# Connectors.net
KiCad netlist of a schematic drawn in Altium Designer
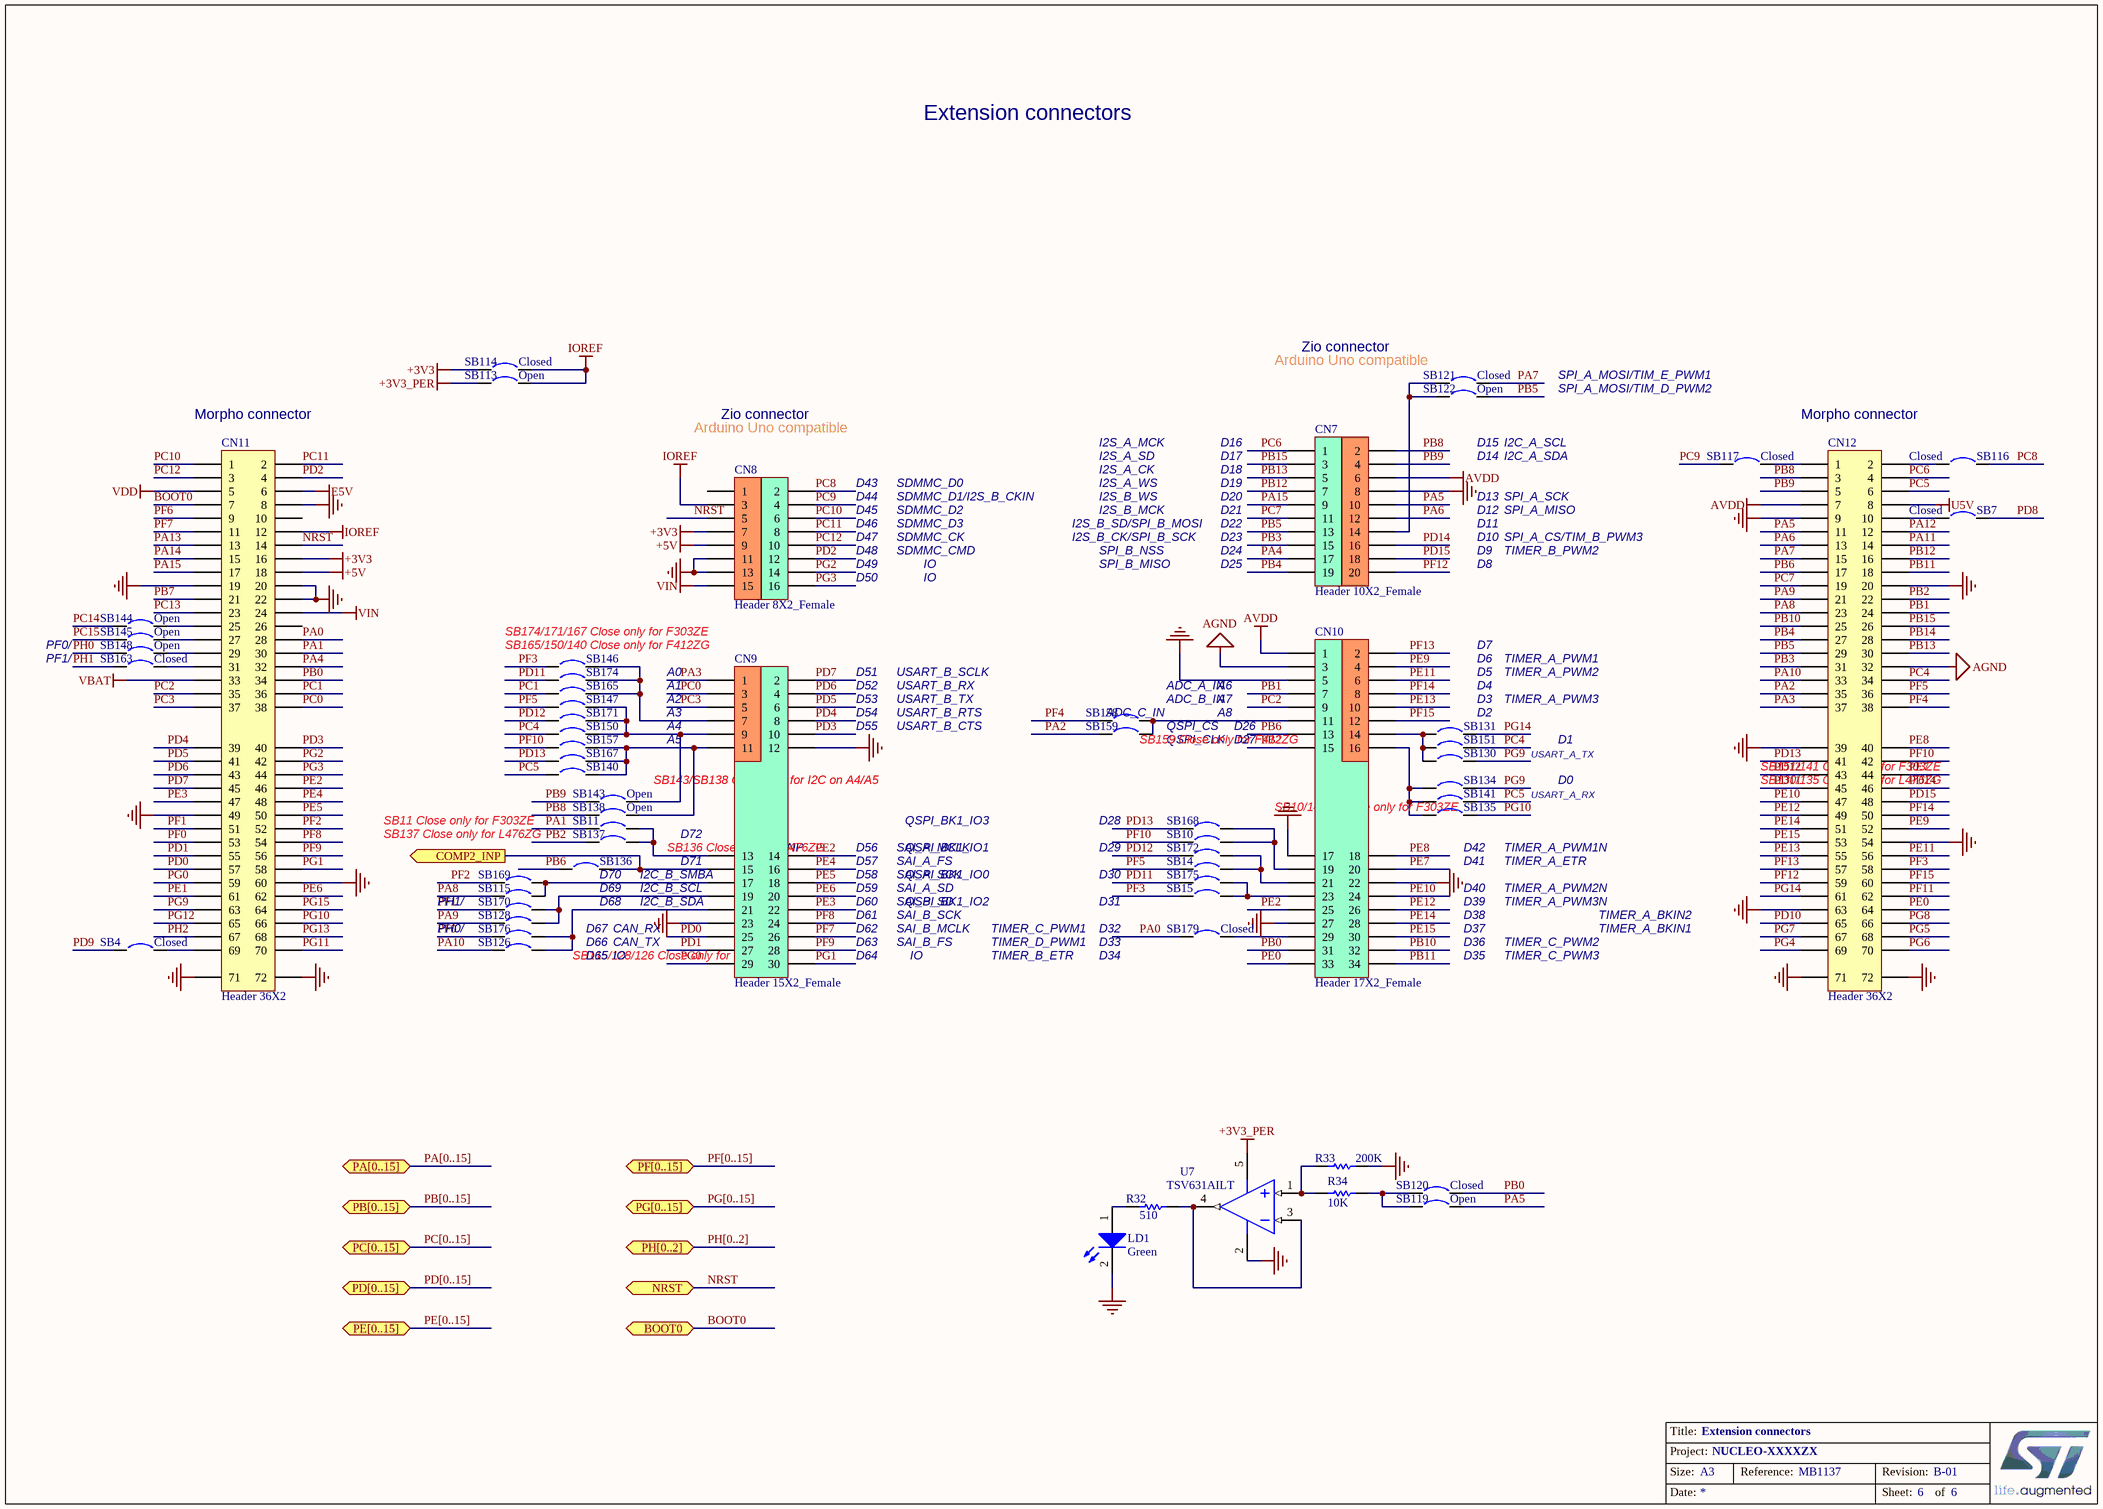
[diagram p0: Connectors.SchDoc]

(export (version "E")
  (design (tool "Eeschema 10.0.6"))
  (components
    (comp (ref "CN7")
      (value "Header 10X2_Female")
      (footprint "HDR_10x2_2R54_V_F")
      (description "Header, 10-Pin, Dual row,female")
      (fields (field (name "PUBLISHER") "Altium Limited"))
      (libsource (lib "MB1137") (part "Header 10X2_Female"))
    )
    (comp (ref "CN8")
      (value "Header 8X2_Female")
      (footprint "HDR_8x2_2R54_V_F")
      (description "Header, 8-Pin, Dual row,female")
      (fields (field (name "PUBLISHER") "Altium Limited"))
      (libsource (lib "MB1137") (part "Header 8X2_Female"))
    )
    (comp (ref "CN9")
      (value "Header 15X2_Female")
      (footprint "HDR_15x2_2R54_V_F")
      (description "Header, 15-Pin, Dual row,female")
      (fields (field (name "PUBLISHER") "Altium Limited"))
      (libsource (lib "MB1137") (part "Header 15X2_Female"))
    )
    (comp (ref "CN10")
      (value "Header 17X2_Female")
      (footprint "HDR_17x2_2R54_V_F")
      (description "Header, 17-Pin, Dual row,female")
      (fields (field (name "PUBLISHER") "Altium Limited"))
      (libsource (lib "MB1137") (part "Header 17X2_Female"))
    )
    (comp (ref "CN11")
      (value "Header 36X2")
      (footprint "HDR_2x36_2R54_V_M")
      (description "Header, 36-Pin, Dual row")
      (fields (field (name "PUBLISHER") "Altium Limited"))
      (libsource (lib "MB1137") (part "Header 36X2"))
    )
    (comp (ref "CN12")
      (value "Header 36X2")
      (footprint "HDR_2x36_2R54_V_M")
      (description "Header, 36-Pin, Dual row")
      (fields (field (name "PUBLISHER") "Altium Limited"))
      (libsource (lib "MB1137") (part "Header 36X2"))
    )
    (comp (ref "LD1")
      (value "Green")
      (footprint "0603D-G")
      (description "Typical RED, GREEN, YELLOW, AMBER GaAs LED")
      (fields (field (name "PUBLISHER") "Altium Limited"))
      (libsource (lib "Miscellaneous Devices") (part "LED2"))
    )
    (comp (ref "R32")
      (value "510")
      (footprint "0603R")
      (description "Resistor")
      (fields (field (name "PUBLISHER") "Altium Limited"))
      (libsource (lib "Miscellaneous Devices") (part "Res1"))
    )
    (comp (ref "R33")
      (value "200K")
      (footprint "0603R")
      (description "Resistor")
      (fields (field (name "PUBLISHER") "Altium Limited"))
      (libsource (lib "Miscellaneous Devices") (part "res1"))
    )
    (comp (ref "R34")
      (value "10K")
      (footprint "0603R")
      (description "Resistor")
      (fields (field (name "PUBLISHER") "Altium Limited"))
      (libsource (lib "Miscellaneous Devices") (part "res1"))
    )
    (comp (ref "SB4")
      (value "Closed")
      (footprint "SB_0603")
      (description "Circuit Breaker")
      (fields (field (name "PUBLISHER") "Altium Limited"))
      (libsource (lib "MB1167") (part "Circuit Breaker_close"))
    )
    (comp (ref "SB7")
      (value "Closed")
      (footprint "SB_0603")
      (description "Circuit Breaker")
      (fields (field (name "PUBLISHER") "Altium Limited"))
      (libsource (lib "MB1167") (part "Circuit Breaker_close"))
    )
    (comp (ref "SB10")
      (value "Circuit Breaker")
      (footprint "SB_0603")
      (fields (field (name "PUBLISHER") "Altium Limited"))
      (libsource (lib "") (part "Circuit Breaker_1"))
    )
    (comp (ref "SB11")
      (value "Circuit Breaker")
      (footprint "SB_0603")
      (fields (field (name "PUBLISHER") "Altium Limited"))
      (libsource (lib "MCD_TOOLS") (part "Circuit Breaker"))
    )
    (comp (ref "SB14")
      (value "Circuit Breaker")
      (footprint "SB_0603")
      (fields (field (name "PUBLISHER") "Altium Limited"))
      (libsource (lib "") (part "Circuit Breaker_1"))
    )
    (comp (ref "SB15")
      (value "Circuit Breaker")
      (footprint "SB_0603")
      (fields (field (name "PUBLISHER") "Altium Limited"))
      (libsource (lib "") (part "Circuit Breaker_1"))
    )
    (comp (ref "SB113")
      (value "Open")
      (footprint "SB_0603")
      (description "Circuit Breaker")
      (fields (field (name "PUBLISHER") "Altium Limited"))
      (libsource (lib "MB1167") (part "Circuit Breaker"))
    )
    (comp (ref "SB114")
      (value "Closed")
      (footprint "SB_0603")
      (description "Circuit Breaker")
      (fields (field (name "PUBLISHER") "Altium Limited"))
      (libsource (lib "MB1167") (part "Circuit Breaker_close"))
    )
    (comp (ref "SB115")
      (value "Circuit Breaker")
      (footprint "SB_0603")
      (fields (field (name "PUBLISHER") "Altium Limited"))
      (libsource (lib "MCD_TOOLS") (part "Circuit Breaker"))
    )
    (comp (ref "SB116")
      (value "Closed")
      (footprint "SB_0603")
      (description "Circuit Breaker")
      (fields (field (name "PUBLISHER") "Altium Limited"))
      (libsource (lib "") (part "Circuit Breaker_close_1"))
    )
    (comp (ref "SB117")
      (value "Closed")
      (footprint "SB_0603")
      (description "Circuit Breaker")
      (fields (field (name "PUBLISHER") "Altium Limited"))
      (libsource (lib "MB1167") (part "Circuit Breaker_close"))
    )
    (comp (ref "SB119")
      (value "Open")
      (footprint "SB_0603")
      (description "Circuit Breaker")
      (fields (field (name "PUBLISHER") "Altium Limited"))
      (libsource (lib "MB1167") (part "Circuit Breaker"))
    )
    (comp (ref "SB120")
      (value "Closed")
      (footprint "SB_0603")
      (description "Circuit Breaker")
      (fields (field (name "PUBLISHER") "Altium Limited"))
      (libsource (lib "") (part "Circuit Breaker_close_1"))
    )
    (comp (ref "SB121")
      (value "Closed")
      (footprint "SB_0603")
      (description "Circuit Breaker")
      (fields (field (name "PUBLISHER") "Altium Limited"))
      (libsource (lib "MB1167") (part "Circuit Breaker_close"))
    )
    (comp (ref "SB122")
      (value "Open")
      (footprint "SB_0603")
      (description "Circuit Breaker")
      (fields (field (name "PUBLISHER") "Altium Limited"))
      (libsource (lib "MB1167") (part "Circuit Breaker"))
    )
    (comp (ref "SB126")
      (value "Circuit Breaker")
      (footprint "SB_0603")
      (fields (field (name "PUBLISHER") "Altium Limited"))
      (libsource (lib "MCD_TOOLS") (part "Circuit Breaker"))
    )
    (comp (ref "SB128")
      (value "Circuit Breaker")
      (footprint "SB_0603")
      (fields (field (name "PUBLISHER") "Altium Limited"))
      (libsource (lib "MCD_TOOLS") (part "Circuit Breaker"))
    )
    (comp (ref "SB130")
      (value "Circuit Breaker")
      (footprint "SB_0603")
      (fields (field (name "PUBLISHER") "Altium Limited"))
      (libsource (lib "MCD_TOOLS") (part "Circuit Breaker"))
    )
    (comp (ref "SB131")
      (value "Circuit Breaker")
      (footprint "SB_0603")
      (fields (field (name "PUBLISHER") "Altium Limited"))
      (libsource (lib "MCD_TOOLS") (part "Circuit Breaker"))
    )
    (comp (ref "SB134")
      (value "Circuit Breaker")
      (footprint "SB_0603")
      (fields (field (name "PUBLISHER") "Altium Limited"))
      (libsource (lib "MCD_TOOLS") (part "Circuit Breaker"))
    )
    (comp (ref "SB135")
      (value "Circuit Breaker")
      (footprint "SB_0603")
      (fields (field (name "PUBLISHER") "Altium Limited"))
      (libsource (lib "MCD_TOOLS") (part "Circuit Breaker"))
    )
    (comp (ref "SB136")
      (value "Circuit Breaker")
      (footprint "SB_0603")
      (fields (field (name "PUBLISHER") "Altium Limited"))
      (libsource (lib "MCD_TOOLS") (part "Circuit Breaker"))
    )
    (comp (ref "SB137")
      (value "Circuit Breaker")
      (footprint "SB_0603")
      (fields (field (name "PUBLISHER") "Altium Limited"))
      (libsource (lib "MCD_TOOLS") (part "Circuit Breaker"))
    )
    (comp (ref "SB138")
      (value "Open")
      (footprint "SB_0603")
      (description "Circuit Breaker")
      (fields (field (name "PUBLISHER") "Altium Limited"))
      (libsource (lib "") (part "Circuit Breaker_1"))
    )
    (comp (ref "SB140")
      (value "Circuit Breaker")
      (footprint "SB_0603")
      (fields (field (name "PUBLISHER") "Altium Limited"))
      (libsource (lib "MCD_TOOLS") (part "Circuit Breaker"))
    )
    (comp (ref "SB141")
      (value "Circuit Breaker")
      (footprint "SB_0603")
      (fields (field (name "PUBLISHER") "Altium Limited"))
      (libsource (lib "MCD_TOOLS") (part "Circuit Breaker"))
    )
    (comp (ref "SB143")
      (value "Open")
      (footprint "SB_0603")
      (description "Circuit Breaker")
      (fields (field (name "PUBLISHER") "Altium Limited"))
      (libsource (lib "") (part "Circuit Breaker_1"))
    )
    (comp (ref "SB144")
      (value "Open")
      (footprint "SB_0603")
      (description "Circuit Breaker")
      (fields (field (name "PUBLISHER") "Altium Limited"))
      (libsource (lib "MB1167") (part "Circuit Breaker"))
    )
    (comp (ref "SB145")
      (value "Open")
      (footprint "SB_0603")
      (description "Circuit Breaker")
      (fields (field (name "PUBLISHER") "Altium Limited"))
      (libsource (lib "MB1167") (part "Circuit Breaker"))
    )
    (comp (ref "SB146")
      (value "Circuit Breaker")
      (footprint "SB_0603")
      (fields (field (name "PUBLISHER") "Altium Limited"))
      (libsource (lib "MCD_TOOLS") (part "Circuit Breaker"))
    )
    (comp (ref "SB147")
      (value "Circuit Breaker")
      (footprint "SB_0603")
      (fields (field (name "PUBLISHER") "Altium Limited"))
      (libsource (lib "MCD_TOOLS") (part "Circuit Breaker"))
    )
    (comp (ref "SB148")
      (value "Open")
      (footprint "SB_0603")
      (description "Circuit Breaker")
      (fields (field (name "PUBLISHER") "Altium Limited"))
      (libsource (lib "MB1167") (part "Circuit Breaker"))
    )
    (comp (ref "SB150")
      (value "Circuit Breaker")
      (footprint "SB_0603")
      (fields (field (name "PUBLISHER") "Altium Limited"))
      (libsource (lib "MCD_TOOLS") (part "Circuit Breaker"))
    )
    (comp (ref "SB151")
      (value "Circuit Breaker")
      (footprint "SB_0603")
      (fields (field (name "PUBLISHER") "Altium Limited"))
      (libsource (lib "MCD_TOOLS") (part "Circuit Breaker"))
    )
    (comp (ref "SB157")
      (value "Circuit Breaker")
      (footprint "SB_0603")
      (fields (field (name "PUBLISHER") "Altium Limited"))
      (libsource (lib "MCD_TOOLS") (part "Circuit Breaker"))
    )
    (comp (ref "SB158")
      (value "Circuit Breaker")
      (footprint "SB_0603")
      (fields (field (name "PUBLISHER") "Altium Limited"))
      (libsource (lib "") (part "Circuit Breaker_1"))
    )
    (comp (ref "SB159")
      (value "Circuit Breaker")
      (footprint "SB_0603")
      (fields (field (name "PUBLISHER") "Altium Limited"))
      (libsource (lib "") (part "Circuit Breaker_1"))
    )
    (comp (ref "SB163")
      (value "Closed")
      (footprint "SB_0603")
      (description "Circuit Breaker")
      (fields (field (name "PUBLISHER") "Altium Limited"))
      (libsource (lib "MB1167") (part "Circuit Breaker_close"))
    )
    (comp (ref "SB165")
      (value "Circuit Breaker")
      (footprint "SB_0603")
      (fields (field (name "PUBLISHER") "Altium Limited"))
      (libsource (lib "MCD_TOOLS") (part "Circuit Breaker"))
    )
    (comp (ref "SB167")
      (value "Circuit Breaker")
      (footprint "SB_0603")
      (fields (field (name "PUBLISHER") "Altium Limited"))
      (libsource (lib "MCD_TOOLS") (part "Circuit Breaker"))
    )
    (comp (ref "SB168")
      (value "Circuit Breaker")
      (footprint "SB_0603")
      (fields (field (name "PUBLISHER") "Altium Limited"))
      (libsource (lib "") (part "Circuit Breaker_1"))
    )
    (comp (ref "SB169")
      (value "Circuit Breaker")
      (footprint "SB_0603")
      (fields (field (name "PUBLISHER") "Altium Limited"))
      (libsource (lib "MCD_TOOLS") (part "Circuit Breaker"))
    )
    (comp (ref "SB170")
      (value "Circuit Breaker")
      (footprint "SB_0603")
      (fields (field (name "PUBLISHER") "Altium Limited"))
      (libsource (lib "MCD_TOOLS") (part "Circuit Breaker"))
    )
    (comp (ref "SB171")
      (value "Circuit Breaker")
      (footprint "SB_0603")
      (fields (field (name "PUBLISHER") "Altium Limited"))
      (libsource (lib "MCD_TOOLS") (part "Circuit Breaker"))
    )
    (comp (ref "SB172")
      (value "Circuit Breaker")
      (footprint "SB_0603")
      (fields (field (name "PUBLISHER") "Altium Limited"))
      (libsource (lib "") (part "Circuit Breaker_1"))
    )
    (comp (ref "SB174")
      (value "Circuit Breaker")
      (footprint "SB_0603")
      (fields (field (name "PUBLISHER") "Altium Limited"))
      (libsource (lib "MCD_TOOLS") (part "Circuit Breaker"))
    )
    (comp (ref "SB175")
      (value "Circuit Breaker")
      (footprint "SB_0603")
      (fields (field (name "PUBLISHER") "Altium Limited"))
      (libsource (lib "") (part "Circuit Breaker_1"))
    )
    (comp (ref "SB176")
      (value "Circuit Breaker")
      (footprint "SB_0603")
      (fields (field (name "PUBLISHER") "Altium Limited"))
      (libsource (lib "MCD_TOOLS") (part "Circuit Breaker"))
    )
    (comp (ref "SB179")
      (value "Closed")
      (footprint "SB_0603")
      (description "Circuit Breaker")
      (fields (field (name "PUBLISHER") "Altium Limited"))
      (libsource (lib "MB1167") (part "Circuit Breaker_close"))
    )
    (comp (ref "U7")
      (value "TSV631AILT")
      (footprint "SOT-23-5L")
      (libsource (lib "MB988") (part "TSV631AILT"))
    )
  )
  (nets
    (net (code "1") (name "+3V3") (class "Default")
      (node (ref "CN11") (pin "16") (pinfunction "16_16") (pintype "passive"))
      (node (ref "CN8") (pin "7") (pinfunction "7_7") (pintype "passive"))
      (node (ref "SB114") (pin "1") (pinfunction "1_1") (pintype "passive"))
    )
    (net (code "2") (name "+3V3_PER") (class "Default")
      (node (ref "SB113") (pin "1") (pinfunction "1_1") (pintype "passive"))
      (node (ref "U7") (pin "5") (pinfunction "VCC_5") (pintype "power_in"))
    )
    (net (code "3") (name "+5V") (class "Default")
      (node (ref "CN11") (pin "18") (pinfunction "18_18") (pintype "passive"))
      (node (ref "CN8") (pin "9") (pinfunction "9_9") (pintype "passive"))
    )
    (net (code "4") (name "/BOOT0") (class "Default")
      (node (ref "CN11") (pin "7") (pinfunction "7_7") (pintype "passive"))
    )
    (net (code "5") (name "/COMP2_INP") (class "Default")
      (node (ref "CN9") (pin "15") (pinfunction "15_15") (pintype "passive"))
      (node (ref "SB136") (pin "1") (pinfunction "1_1") (pintype "passive"))
    )
    (net (code "6") (name "/NRST") (class "Default")
      (node (ref "CN11") (pin "14") (pinfunction "14_14") (pintype "passive"))
      (node (ref "CN8") (pin "5") (pinfunction "5_5") (pintype "passive"))
    )
    (net (code "7") (name "/PA0") (class "Default")
      (node (ref "CN11") (pin "28") (pinfunction "28_28") (pintype "passive"))
      (node (ref "SB179") (pin "1") (pinfunction "1_1") (pintype "passive"))
    )
    (net (code "8") (name "/PA1") (class "Default")
      (node (ref "CN11") (pin "30") (pinfunction "30_30") (pintype "passive"))
      (node (ref "SB11") (pin "2") (pinfunction "2_2") (pintype "passive"))
    )
    (net (code "9") (name "/PA2") (class "Default")
      (node (ref "CN12") (pin "35") (pinfunction "35_35") (pintype "passive"))
      (node (ref "SB159") (pin "1") (pinfunction "1_1") (pintype "passive"))
    )
    (net (code "10") (name "/PA3") (class "Default")
      (node (ref "CN12") (pin "37") (pinfunction "37_37") (pintype "passive"))
      (node (ref "CN9") (pin "1") (pinfunction "1_1") (pintype "passive"))
    )
    (net (code "11") (name "/PA4") (class "Default")
      (node (ref "CN11") (pin "32") (pinfunction "32_32") (pintype "passive"))
      (node (ref "CN7") (pin "17") (pinfunction "17_17") (pintype "passive"))
    )
    (net (code "12") (name "/PA5") (class "Default")
      (node (ref "CN12") (pin "11") (pinfunction "11_11") (pintype "passive"))
      (node (ref "CN7") (pin "10") (pinfunction "10_10") (pintype "passive"))
      (node (ref "SB119") (pin "2") (pinfunction "2_2") (pintype "passive"))
    )
    (net (code "13") (name "/PA6") (class "Default")
      (node (ref "CN12") (pin "13") (pinfunction "13_13") (pintype "passive"))
      (node (ref "CN7") (pin "12") (pinfunction "12_12") (pintype "passive"))
    )
    (net (code "14") (name "/PA7") (class "Default")
      (node (ref "CN12") (pin "15") (pinfunction "15_15") (pintype "passive"))
      (node (ref "SB121") (pin "2") (pinfunction "2_2") (pintype "passive"))
    )
    (net (code "15") (name "/PA8") (class "Default")
      (node (ref "CN12") (pin "23") (pinfunction "23_23") (pintype "passive"))
      (node (ref "SB115") (pin "2") (pinfunction "2_2") (pintype "passive"))
    )
    (net (code "16") (name "/PA9") (class "Default")
      (node (ref "CN12") (pin "21") (pinfunction "21_21") (pintype "passive"))
      (node (ref "SB128") (pin "2") (pinfunction "2_2") (pintype "passive"))
    )
    (net (code "17") (name "/PA10") (class "Default")
      (node (ref "CN12") (pin "33") (pinfunction "33_33") (pintype "passive"))
      (node (ref "SB126") (pin "2") (pinfunction "2_2") (pintype "passive"))
    )
    (net (code "18") (name "/PA11") (class "Default")
      (node (ref "CN12") (pin "14") (pinfunction "14_14") (pintype "passive"))
    )
    (net (code "19") (name "/PA12") (class "Default")
      (node (ref "CN12") (pin "12") (pinfunction "12_12") (pintype "passive"))
    )
    (net (code "20") (name "/PA13") (class "Default")
      (node (ref "CN11") (pin "13") (pinfunction "13_13") (pintype "passive"))
    )
    (net (code "21") (name "/PA14") (class "Default")
      (node (ref "CN11") (pin "15") (pinfunction "15_15") (pintype "passive"))
    )
    (net (code "22") (name "/PA15") (class "Default")
      (node (ref "CN11") (pin "17") (pinfunction "17_17") (pintype "passive"))
      (node (ref "CN7") (pin "9") (pinfunction "9_9") (pintype "passive"))
    )
    (net (code "24") (name "/PB0") (class "Default")
      (node (ref "CN10") (pin "31") (pinfunction "31_31") (pintype "passive"))
      (node (ref "CN11") (pin "34") (pinfunction "34_34") (pintype "passive"))
      (node (ref "SB120") (pin "1") (pinfunction "1_1") (pintype "passive"))
    )
    (net (code "25") (name "/PB1") (class "Default")
      (node (ref "CN10") (pin "7") (pinfunction "7_7") (pintype "passive"))
      (node (ref "CN12") (pin "24") (pinfunction "24_24") (pintype "passive"))
    )
    (net (code "26") (name "/PB2") (class "Default")
      (node (ref "CN10") (pin "15") (pinfunction "15_15") (pintype "passive"))
      (node (ref "CN12") (pin "22") (pinfunction "22_22") (pintype "passive"))
      (node (ref "SB137") (pin "2") (pinfunction "2_2") (pintype "passive"))
    )
    (net (code "27") (name "/PB3") (class "Default")
      (node (ref "CN12") (pin "31") (pinfunction "31_31") (pintype "passive"))
      (node (ref "CN7") (pin "15") (pinfunction "15_15") (pintype "passive"))
    )
    (net (code "28") (name "/PB4") (class "Default")
      (node (ref "CN12") (pin "27") (pinfunction "27_27") (pintype "passive"))
      (node (ref "CN7") (pin "19") (pinfunction "19_19") (pintype "passive"))
    )
    (net (code "29") (name "/PB5") (class "Default")
      (node (ref "CN12") (pin "29") (pinfunction "29_29") (pintype "passive"))
      (node (ref "CN7") (pin "13") (pinfunction "13_13") (pintype "passive"))
      (node (ref "SB122") (pin "2") (pinfunction "2_2") (pintype "passive"))
    )
    (net (code "30") (name "/PB6") (class "Default")
      (node (ref "CN10") (pin "13") (pinfunction "13_13") (pintype "passive"))
      (node (ref "CN12") (pin "17") (pinfunction "17_17") (pintype "passive"))
      (node (ref "SB136") (pin "2") (pinfunction "2_2") (pintype "passive"))
    )
    (net (code "31") (name "/PB7") (class "Default")
      (node (ref "CN11") (pin "21") (pinfunction "21_21") (pintype "passive"))
    )
    (net (code "32") (name "/PB8") (class "Default")
      (node (ref "CN12") (pin "3") (pinfunction "3_3") (pintype "passive"))
      (node (ref "CN7") (pin "2") (pinfunction "2_2") (pintype "passive"))
      (node (ref "SB138") (pin "2") (pinfunction "2_2") (pintype "passive"))
    )
    (net (code "33") (name "/PB9") (class "Default")
      (node (ref "CN12") (pin "5") (pinfunction "5_5") (pintype "passive"))
      (node (ref "CN7") (pin "4") (pinfunction "4_4") (pintype "passive"))
      (node (ref "SB143") (pin "2") (pinfunction "2_2") (pintype "passive"))
    )
    (net (code "34") (name "/PB10") (class "Default")
      (node (ref "CN10") (pin "32") (pinfunction "32_32") (pintype "passive"))
      (node (ref "CN12") (pin "25") (pinfunction "25_25") (pintype "passive"))
    )
    (net (code "35") (name "/PB11") (class "Default")
      (node (ref "CN10") (pin "34") (pinfunction "34_34") (pintype "passive"))
      (node (ref "CN12") (pin "18") (pinfunction "18_18") (pintype "passive"))
    )
    (net (code "36") (name "/PB12") (class "Default")
      (node (ref "CN12") (pin "16") (pinfunction "16_16") (pintype "passive"))
      (node (ref "CN7") (pin "7") (pinfunction "7_7") (pintype "passive"))
    )
    (net (code "37") (name "/PB13") (class "Default")
      (node (ref "CN12") (pin "30") (pinfunction "30_30") (pintype "passive"))
      (node (ref "CN7") (pin "5") (pinfunction "5_5") (pintype "passive"))
    )
    (net (code "38") (name "/PB14") (class "Default")
      (node (ref "CN12") (pin "28") (pinfunction "28_28") (pintype "passive"))
    )
    (net (code "39") (name "/PB15") (class "Default")
      (node (ref "CN12") (pin "26") (pinfunction "26_26") (pintype "passive"))
      (node (ref "CN7") (pin "3") (pinfunction "3_3") (pintype "passive"))
    )
    (net (code "41") (name "/PC0") (class "Default")
      (node (ref "CN11") (pin "38") (pinfunction "38_38") (pintype "passive"))
      (node (ref "CN9") (pin "3") (pinfunction "3_3") (pintype "passive"))
    )
    (net (code "42") (name "/PC1") (class "Default")
      (node (ref "CN11") (pin "36") (pinfunction "36_36") (pintype "passive"))
      (node (ref "SB165") (pin "2") (pinfunction "2_2") (pintype "passive"))
    )
    (net (code "43") (name "/PC2") (class "Default")
      (node (ref "CN10") (pin "9") (pinfunction "9_9") (pintype "passive"))
      (node (ref "CN11") (pin "35") (pinfunction "35_35") (pintype "passive"))
    )
    (net (code "44") (name "/PC3") (class "Default")
      (node (ref "CN11") (pin "37") (pinfunction "37_37") (pintype "passive"))
      (node (ref "CN9") (pin "5") (pinfunction "5_5") (pintype "passive"))
    )
    (net (code "45") (name "/PC4") (class "Default")
      (node (ref "CN12") (pin "34") (pinfunction "34_34") (pintype "passive"))
      (node (ref "SB150") (pin "2") (pinfunction "2_2") (pintype "passive"))
      (node (ref "SB151") (pin "1") (pinfunction "1_1") (pintype "passive"))
    )
    (net (code "46") (name "/PC5") (class "Default")
      (node (ref "CN12") (pin "6") (pinfunction "6_6") (pintype "passive"))
      (node (ref "SB140") (pin "2") (pinfunction "2_2") (pintype "passive"))
      (node (ref "SB141") (pin "1") (pinfunction "1_1") (pintype "passive"))
    )
    (net (code "47") (name "/PC6") (class "Default")
      (node (ref "CN12") (pin "4") (pinfunction "4_4") (pintype "passive"))
      (node (ref "CN7") (pin "1") (pinfunction "1_1") (pintype "passive"))
    )
    (net (code "48") (name "/PC7") (class "Default")
      (node (ref "CN12") (pin "19") (pinfunction "19_19") (pintype "passive"))
      (node (ref "CN7") (pin "11") (pinfunction "11_11") (pintype "passive"))
    )
    (net (code "49") (name "/PC8") (class "Default")
      (node (ref "CN8") (pin "2") (pinfunction "2_2") (pintype "passive"))
      (node (ref "SB116") (pin "1") (pinfunction "1_1") (pintype "passive"))
    )
    (net (code "50") (name "/PC9") (class "Default")
      (node (ref "CN8") (pin "4") (pinfunction "4_4") (pintype "passive"))
      (node (ref "SB117") (pin "1") (pinfunction "1_1") (pintype "passive"))
    )
    (net (code "51") (name "/PC10") (class "Default")
      (node (ref "CN11") (pin "1") (pinfunction "1_1") (pintype "passive"))
      (node (ref "CN8") (pin "6") (pinfunction "6_6") (pintype "passive"))
    )
    (net (code "52") (name "/PC11") (class "Default")
      (node (ref "CN11") (pin "2") (pinfunction "2_2") (pintype "passive"))
      (node (ref "CN8") (pin "8") (pinfunction "8_8") (pintype "passive"))
    )
    (net (code "53") (name "/PC12") (class "Default")
      (node (ref "CN11") (pin "3") (pinfunction "3_3") (pintype "passive"))
      (node (ref "CN8") (pin "10") (pinfunction "10_10") (pintype "passive"))
    )
    (net (code "54") (name "/PC13") (class "Default")
      (node (ref "CN11") (pin "23") (pinfunction "23_23") (pintype "passive"))
    )
    (net (code "55") (name "/PC14") (class "Default")
      (node (ref "SB144") (pin "1") (pinfunction "1_1") (pintype "passive"))
    )
    (net (code "56") (name "/PC15") (class "Default")
      (node (ref "SB145") (pin "1") (pinfunction "1_1") (pintype "passive"))
    )
    (net (code "58") (name "/PD0") (class "Default")
      (node (ref "CN11") (pin "57") (pinfunction "57_57") (pintype "passive"))
      (node (ref "CN9") (pin "25") (pinfunction "25_25") (pintype "passive"))
    )
    (net (code "59") (name "/PD1") (class "Default")
      (node (ref "CN11") (pin "55") (pinfunction "55_55") (pintype "passive"))
      (node (ref "CN9") (pin "27") (pinfunction "27_27") (pintype "passive"))
    )
    (net (code "60") (name "/PD2") (class "Default")
      (node (ref "CN11") (pin "4") (pinfunction "4_4") (pintype "passive"))
      (node (ref "CN8") (pin "12") (pinfunction "12_12") (pintype "passive"))
    )
    (net (code "61") (name "/PD3") (class "Default")
      (node (ref "CN11") (pin "40") (pinfunction "40_40") (pintype "passive"))
      (node (ref "CN9") (pin "10") (pinfunction "10_10") (pintype "passive"))
    )
    (net (code "62") (name "/PD4") (class "Default")
      (node (ref "CN11") (pin "39") (pinfunction "39_39") (pintype "passive"))
      (node (ref "CN9") (pin "8") (pinfunction "8_8") (pintype "passive"))
    )
    (net (code "63") (name "/PD5") (class "Default")
      (node (ref "CN11") (pin "41") (pinfunction "41_41") (pintype "passive"))
      (node (ref "CN9") (pin "6") (pinfunction "6_6") (pintype "passive"))
    )
    (net (code "64") (name "/PD6") (class "Default")
      (node (ref "CN11") (pin "43") (pinfunction "43_43") (pintype "passive"))
      (node (ref "CN9") (pin "4") (pinfunction "4_4") (pintype "passive"))
    )
    (net (code "65") (name "/PD7") (class "Default")
      (node (ref "CN11") (pin "45") (pinfunction "45_45") (pintype "passive"))
      (node (ref "CN9") (pin "2") (pinfunction "2_2") (pintype "passive"))
    )
    (net (code "66") (name "/PD8") (class "Default")
      (node (ref "SB7") (pin "2") (pinfunction "2_2") (pintype "passive"))
    )
    (net (code "67") (name "/PD9") (class "Default")
      (node (ref "SB4") (pin "1") (pinfunction "1_1") (pintype "passive"))
    )
    (net (code "68") (name "/PD10") (class "Default")
      (node (ref "CN12") (pin "65") (pinfunction "65_65") (pintype "passive"))
    )
    (net (code "69") (name "/PD11") (class "Default")
      (node (ref "CN12") (pin "45") (pinfunction "45_45") (pintype "passive"))
      (node (ref "SB174") (pin "2") (pinfunction "2_2") (pintype "passive"))
      (node (ref "SB175") (pin "1") (pinfunction "1_1") (pintype "passive"))
    )
    (net (code "70") (name "/PD12") (class "Default")
      (node (ref "CN12") (pin "43") (pinfunction "43_43") (pintype "passive"))
      (node (ref "SB171") (pin "2") (pinfunction "2_2") (pintype "passive"))
      (node (ref "SB172") (pin "1") (pinfunction "1_1") (pintype "passive"))
    )
    (net (code "71") (name "/PD13") (class "Default")
      (node (ref "CN12") (pin "41") (pinfunction "41_41") (pintype "passive"))
      (node (ref "SB167") (pin "2") (pinfunction "2_2") (pintype "passive"))
      (node (ref "SB168") (pin "1") (pinfunction "1_1") (pintype "passive"))
    )
    (net (code "72") (name "/PD14") (class "Default")
      (node (ref "CN12") (pin "46") (pinfunction "46_46") (pintype "passive"))
      (node (ref "CN7") (pin "16") (pinfunction "16_16") (pintype "passive"))
    )
    (net (code "73") (name "/PD15") (class "Default")
      (node (ref "CN12") (pin "48") (pinfunction "48_48") (pintype "passive"))
      (node (ref "CN7") (pin "18") (pinfunction "18_18") (pintype "passive"))
    )
    (net (code "75") (name "/PE0") (class "Default")
      (node (ref "CN10") (pin "33") (pinfunction "33_33") (pintype "passive"))
      (node (ref "CN12") (pin "64") (pinfunction "64_64") (pintype "passive"))
    )
    (net (code "76") (name "/PE1") (class "Default")
      (node (ref "CN11") (pin "61") (pinfunction "61_61") (pintype "passive"))
    )
    (net (code "77") (name "/PE2") (class "Default")
      (node (ref "CN10") (pin "25") (pinfunction "25_25") (pintype "passive"))
      (node (ref "CN11") (pin "46") (pinfunction "46_46") (pintype "passive"))
      (node (ref "CN9") (pin "14") (pinfunction "14_14") (pintype "passive"))
    )
    (net (code "78") (name "/PE3") (class "Default")
      (node (ref "CN11") (pin "47") (pinfunction "47_47") (pintype "passive"))
      (node (ref "CN9") (pin "22") (pinfunction "22_22") (pintype "passive"))
    )
    (net (code "79") (name "/PE4") (class "Default")
      (node (ref "CN11") (pin "48") (pinfunction "48_48") (pintype "passive"))
      (node (ref "CN9") (pin "16") (pinfunction "16_16") (pintype "passive"))
    )
    (net (code "80") (name "/PE5") (class "Default")
      (node (ref "CN11") (pin "50") (pinfunction "50_50") (pintype "passive"))
      (node (ref "CN9") (pin "18") (pinfunction "18_18") (pintype "passive"))
    )
    (net (code "81") (name "/PE6") (class "Default")
      (node (ref "CN11") (pin "62") (pinfunction "62_62") (pintype "passive"))
      (node (ref "CN9") (pin "20") (pinfunction "20_20") (pintype "passive"))
    )
    (net (code "82") (name "/PE7") (class "Default")
      (node (ref "CN10") (pin "20") (pinfunction "20_20") (pintype "passive"))
      (node (ref "CN12") (pin "44") (pinfunction "44_44") (pintype "passive"))
    )
    (net (code "83") (name "/PE8") (class "Default")
      (node (ref "CN10") (pin "18") (pinfunction "18_18") (pintype "passive"))
      (node (ref "CN12") (pin "40") (pinfunction "40_40") (pintype "passive"))
    )
    (net (code "84") (name "/PE9") (class "Default")
      (node (ref "CN10") (pin "4") (pinfunction "4_4") (pintype "passive"))
      (node (ref "CN12") (pin "52") (pinfunction "52_52") (pintype "passive"))
    )
    (net (code "85") (name "/PE10") (class "Default")
      (node (ref "CN10") (pin "24") (pinfunction "24_24") (pintype "passive"))
      (node (ref "CN12") (pin "47") (pinfunction "47_47") (pintype "passive"))
    )
    (net (code "86") (name "/PE11") (class "Default")
      (node (ref "CN10") (pin "6") (pinfunction "6_6") (pintype "passive"))
      (node (ref "CN12") (pin "56") (pinfunction "56_56") (pintype "passive"))
    )
    (net (code "87") (name "/PE12") (class "Default")
      (node (ref "CN10") (pin "26") (pinfunction "26_26") (pintype "passive"))
      (node (ref "CN12") (pin "49") (pinfunction "49_49") (pintype "passive"))
    )
    (net (code "88") (name "/PE13") (class "Default")
      (node (ref "CN10") (pin "10") (pinfunction "10_10") (pintype "passive"))
      (node (ref "CN12") (pin "55") (pinfunction "55_55") (pintype "passive"))
    )
    (net (code "89") (name "/PE14") (class "Default")
      (node (ref "CN10") (pin "28") (pinfunction "28_28") (pintype "passive"))
      (node (ref "CN12") (pin "51") (pinfunction "51_51") (pintype "passive"))
    )
    (net (code "90") (name "/PE15") (class "Default")
      (node (ref "CN10") (pin "30") (pinfunction "30_30") (pintype "passive"))
      (node (ref "CN12") (pin "53") (pinfunction "53_53") (pintype "passive"))
    )
    (net (code "92") (name "/PF0") (class "Default")
      (node (ref "CN11") (pin "53") (pinfunction "53_53") (pintype "passive"))
      (node (ref "SB176") (pin "2") (pinfunction "2_2") (pintype "passive"))
    )
    (net (code "93") (name "/PF1") (class "Default")
      (node (ref "CN11") (pin "51") (pinfunction "51_51") (pintype "passive"))
      (node (ref "SB170") (pin "2") (pinfunction "2_2") (pintype "passive"))
    )
    (net (code "94") (name "/PF2") (class "Default")
      (node (ref "CN11") (pin "52") (pinfunction "52_52") (pintype "passive"))
      (node (ref "SB169") (pin "2") (pinfunction "2_2") (pintype "passive"))
    )
    (net (code "95") (name "/PF3") (class "Default")
      (node (ref "CN12") (pin "58") (pinfunction "58_58") (pintype "passive"))
      (node (ref "SB146") (pin "2") (pinfunction "2_2") (pintype "passive"))
      (node (ref "SB15") (pin "1") (pinfunction "1_1") (pintype "passive"))
    )
    (net (code "96") (name "/PF4") (class "Default")
      (node (ref "CN12") (pin "38") (pinfunction "38_38") (pintype "passive"))
      (node (ref "SB158") (pin "1") (pinfunction "1_1") (pintype "passive"))
    )
    (net (code "97") (name "/PF5") (class "Default")
      (node (ref "CN12") (pin "36") (pinfunction "36_36") (pintype "passive"))
      (node (ref "SB14") (pin "1") (pinfunction "1_1") (pintype "passive"))
      (node (ref "SB147") (pin "2") (pinfunction "2_2") (pintype "passive"))
    )
    (net (code "98") (name "/PF6") (class "Default")
      (node (ref "CN11") (pin "9") (pinfunction "9_9") (pintype "passive"))
    )
    (net (code "99") (name "/PF7") (class "Default")
      (node (ref "CN11") (pin "11") (pinfunction "11_11") (pintype "passive"))
      (node (ref "CN9") (pin "26") (pinfunction "26_26") (pintype "passive"))
    )
    (net (code "100") (name "/PF8") (class "Default")
      (node (ref "CN11") (pin "54") (pinfunction "54_54") (pintype "passive"))
      (node (ref "CN9") (pin "24") (pinfunction "24_24") (pintype "passive"))
    )
    (net (code "101") (name "/PF9") (class "Default")
      (node (ref "CN11") (pin "56") (pinfunction "56_56") (pintype "passive"))
      (node (ref "CN9") (pin "28") (pinfunction "28_28") (pintype "passive"))
    )
    (net (code "102") (name "/PF10") (class "Default")
      (node (ref "CN12") (pin "42") (pinfunction "42_42") (pintype "passive"))
      (node (ref "SB10") (pin "1") (pinfunction "1_1") (pintype "passive"))
      (node (ref "SB157") (pin "2") (pinfunction "2_2") (pintype "passive"))
    )
    (net (code "103") (name "/PF11") (class "Default")
      (node (ref "CN12") (pin "62") (pinfunction "62_62") (pintype "passive"))
    )
    (net (code "104") (name "/PF12") (class "Default")
      (node (ref "CN12") (pin "59") (pinfunction "59_59") (pintype "passive"))
      (node (ref "CN7") (pin "20") (pinfunction "20_20") (pintype "passive"))
    )
    (net (code "105") (name "/PF13") (class "Default")
      (node (ref "CN10") (pin "2") (pinfunction "2_2") (pintype "passive"))
      (node (ref "CN12") (pin "57") (pinfunction "57_57") (pintype "passive"))
    )
    (net (code "106") (name "/PF14") (class "Default")
      (node (ref "CN10") (pin "8") (pinfunction "8_8") (pintype "passive"))
      (node (ref "CN12") (pin "50") (pinfunction "50_50") (pintype "passive"))
    )
    (net (code "107") (name "/PF15") (class "Default")
      (node (ref "CN10") (pin "12") (pinfunction "12_12") (pintype "passive"))
      (node (ref "CN12") (pin "60") (pinfunction "60_60") (pintype "passive"))
    )
    (net (code "109") (name "/PG0") (class "Default")
      (node (ref "CN11") (pin "59") (pinfunction "59_59") (pintype "passive"))
      (node (ref "CN9") (pin "29") (pinfunction "29_29") (pintype "passive"))
    )
    (net (code "110") (name "/PG1") (class "Default")
      (node (ref "CN11") (pin "58") (pinfunction "58_58") (pintype "passive"))
      (node (ref "CN9") (pin "30") (pinfunction "30_30") (pintype "passive"))
    )
    (net (code "111") (name "/PG2") (class "Default")
      (node (ref "CN11") (pin "42") (pinfunction "42_42") (pintype "passive"))
      (node (ref "CN8") (pin "14") (pinfunction "14_14") (pintype "passive"))
    )
    (net (code "112") (name "/PG3") (class "Default")
      (node (ref "CN11") (pin "44") (pinfunction "44_44") (pintype "passive"))
      (node (ref "CN8") (pin "16") (pinfunction "16_16") (pintype "passive"))
    )
    (net (code "113") (name "/PG4") (class "Default")
      (node (ref "CN12") (pin "69") (pinfunction "69_69") (pintype "passive"))
    )
    (net (code "114") (name "/PG5") (class "Default")
      (node (ref "CN12") (pin "68") (pinfunction "68_68") (pintype "passive"))
    )
    (net (code "115") (name "/PG6") (class "Default")
      (node (ref "CN12") (pin "70") (pinfunction "70_70") (pintype "passive"))
    )
    (net (code "116") (name "/PG7") (class "Default")
      (node (ref "CN12") (pin "67") (pinfunction "67_67") (pintype "passive"))
    )
    (net (code "117") (name "/PG8") (class "Default")
      (node (ref "CN12") (pin "66") (pinfunction "66_66") (pintype "passive"))
    )
    (net (code "118") (name "/PG9") (class "Default")
      (node (ref "CN11") (pin "63") (pinfunction "63_63") (pintype "passive"))
      (node (ref "SB130") (pin "1") (pinfunction "1_1") (pintype "passive"))
      (node (ref "SB134") (pin "1") (pinfunction "1_1") (pintype "passive"))
    )
    (net (code "119") (name "/PG10") (class "Default")
      (node (ref "CN11") (pin "66") (pinfunction "66_66") (pintype "passive"))
      (node (ref "SB135") (pin "1") (pinfunction "1_1") (pintype "passive"))
    )
    (net (code "120") (name "/PG11") (class "Default")
      (node (ref "CN11") (pin "70") (pinfunction "70_70") (pintype "passive"))
    )
    (net (code "121") (name "/PG12") (class "Default")
      (node (ref "CN11") (pin "65") (pinfunction "65_65") (pintype "passive"))
    )
    (net (code "122") (name "/PG13") (class "Default")
      (node (ref "CN11") (pin "68") (pinfunction "68_68") (pintype "passive"))
    )
    (net (code "123") (name "/PG14") (class "Default")
      (node (ref "CN12") (pin "61") (pinfunction "61_61") (pintype "passive"))
      (node (ref "SB131") (pin "1") (pinfunction "1_1") (pintype "passive"))
    )
    (net (code "124") (name "/PG15") (class "Default")
      (node (ref "CN11") (pin "64") (pinfunction "64_64") (pintype "passive"))
    )
    (net (code "126") (name "/PH0") (class "Default")
      (node (ref "SB148") (pin "1") (pinfunction "1_1") (pintype "passive"))
    )
    (net (code "127") (name "/PH1") (class "Default")
      (node (ref "SB163") (pin "1") (pinfunction "1_1") (pintype "passive"))
    )
    (net (code "128") (name "/PH2") (class "Default")
      (node (ref "CN11") (pin "67") (pinfunction "67_67") (pintype "passive"))
    )
    (net (code "130") (name "AGND") (class "Default")
      (node (ref "CN10") (pin "3") (pinfunction "3_3") (pintype "passive"))
      (node (ref "CN12") (pin "32") (pinfunction "32_32") (pintype "passive"))
    )
    (net (code "131") (name "AVDD") (class "Default")
      (node (ref "CN10") (pin "1") (pinfunction "1_1") (pintype "passive"))
      (node (ref "CN12") (pin "7") (pinfunction "7_7") (pintype "passive"))
      (node (ref "CN7") (pin "6") (pinfunction "6_6") (pintype "passive"))
    )
    (net (code "132") (name "E5V") (class "Default")
      (node (ref "CN11") (pin "6") (pinfunction "6_6") (pintype "passive"))
    )
    (net (code "133") (name "GND") (class "Default")
      (node (ref "CN10") (pin "17") (pinfunction "17_17") (pintype "passive"))
      (node (ref "CN10") (pin "22") (pinfunction "22_22") (pintype "passive"))
      (node (ref "CN10") (pin "27") (pinfunction "27_27") (pintype "passive"))
      (node (ref "CN10") (pin "5") (pinfunction "5_5") (pintype "passive"))
      (node (ref "CN11") (pin "19") (pinfunction "19_19") (pintype "passive"))
      (node (ref "CN11") (pin "20") (pinfunction "20_20") (pintype "passive"))
      (node (ref "CN11") (pin "22") (pinfunction "22_22") (pintype "passive"))
      (node (ref "CN11") (pin "49") (pinfunction "49_49") (pintype "passive"))
      (node (ref "CN11") (pin "60") (pinfunction "60_60") (pintype "passive"))
      (node (ref "CN11") (pin "71") (pinfunction "71_71") (pintype "passive"))
      (node (ref "CN11") (pin "72") (pinfunction "72_72") (pintype "passive"))
      (node (ref "CN11") (pin "8") (pinfunction "8_8") (pintype "passive"))
      (node (ref "CN12") (pin "20") (pinfunction "20_20") (pintype "passive"))
      (node (ref "CN12") (pin "39") (pinfunction "39_39") (pintype "passive"))
      (node (ref "CN12") (pin "54") (pinfunction "54_54") (pintype "passive"))
      (node (ref "CN12") (pin "63") (pinfunction "63_63") (pintype "passive"))
      (node (ref "CN12") (pin "71") (pinfunction "71_71") (pintype "passive"))
      (node (ref "CN12") (pin "72") (pinfunction "72_72") (pintype "passive"))
      (node (ref "CN12") (pin "9") (pinfunction "9_9") (pintype "passive"))
      (node (ref "CN7") (pin "8") (pinfunction "8_8") (pintype "passive"))
      (node (ref "CN8") (pin "11") (pinfunction "11_11") (pintype "passive"))
      (node (ref "CN8") (pin "13") (pinfunction "13_13") (pintype "passive"))
      (node (ref "CN9") (pin "12") (pinfunction "12_12") (pintype "passive"))
      (node (ref "CN9") (pin "23") (pinfunction "23_23") (pintype "passive"))
      (node (ref "LD1") (pin "2") (pinfunction "K_2") (pintype "passive"))
      (node (ref "R33") (pin "2") (pinfunction "2_2") (pintype "passive"))
      (node (ref "U7") (pin "2") (pinfunction "VDD_2") (pintype "power_in"))
    )
    (net (code "134") (name "IOREF") (class "Default")
      (node (ref "CN11") (pin "12") (pinfunction "12_12") (pintype "passive"))
      (node (ref "CN8") (pin "3") (pinfunction "3_3") (pintype "passive"))
      (node (ref "SB113") (pin "2") (pinfunction "2_2") (pintype "passive"))
      (node (ref "SB114") (pin "2") (pinfunction "2_2") (pintype "passive"))
    )
    (net (code "135") (name "Net-(CN7-Pad14)") (class "Default")
      (node (ref "CN7") (pin "14") (pinfunction "14_14") (pintype "passive"))
      (node (ref "SB121") (pin "1") (pinfunction "1_1") (pintype "passive"))
      (node (ref "SB122") (pin "1") (pinfunction "1_1") (pintype "passive"))
    )
    (net (code "136") (name "Net-(CN9-Pad7)") (class "Default")
      (node (ref "CN9") (pin "7") (pinfunction "7_7") (pintype "passive"))
      (node (ref "SB146") (pin "1") (pinfunction "1_1") (pintype "passive"))
      (node (ref "SB165") (pin "1") (pinfunction "1_1") (pintype "passive"))
      (node (ref "SB174") (pin "1") (pinfunction "1_1") (pintype "passive"))
    )
    (net (code "137") (name "Net-(CN9-Pad9)") (class "Default")
      (node (ref "CN9") (pin "9") (pinfunction "9_9") (pintype "passive"))
      (node (ref "SB143") (pin "1") (pinfunction "1_1") (pintype "passive"))
      (node (ref "SB147") (pin "1") (pinfunction "1_1") (pintype "passive"))
      (node (ref "SB150") (pin "1") (pinfunction "1_1") (pintype "passive"))
      (node (ref "SB171") (pin "1") (pinfunction "1_1") (pintype "passive"))
    )
    (net (code "138") (name "Net-(CN9-Pad11)") (class "Default")
      (node (ref "CN9") (pin "11") (pinfunction "11_11") (pintype "passive"))
      (node (ref "SB138") (pin "1") (pinfunction "1_1") (pintype "passive"))
      (node (ref "SB140") (pin "1") (pinfunction "1_1") (pintype "passive"))
      (node (ref "SB157") (pin "1") (pinfunction "1_1") (pintype "passive"))
      (node (ref "SB167") (pin "1") (pinfunction "1_1") (pintype "passive"))
    )
    (net (code "139") (name "Net-(CN9-Pad13)") (class "Default")
      (node (ref "CN9") (pin "13") (pinfunction "13_13") (pintype "passive"))
      (node (ref "SB11") (pin "1") (pinfunction "1_1") (pintype "passive"))
      (node (ref "SB137") (pin "1") (pinfunction "1_1") (pintype "passive"))
    )
    (net (code "140") (name "Net-(CN9-Pad17)") (class "Default")
      (node (ref "CN9") (pin "17") (pinfunction "17_17") (pintype "passive"))
      (node (ref "SB115") (pin "1") (pinfunction "1_1") (pintype "passive"))
      (node (ref "SB169") (pin "1") (pinfunction "1_1") (pintype "passive"))
    )
    (net (code "141") (name "Net-(CN9-Pad19)") (class "Default")
      (node (ref "CN9") (pin "19") (pinfunction "19_19") (pintype "passive"))
      (node (ref "SB128") (pin "1") (pinfunction "1_1") (pintype "passive"))
      (node (ref "SB170") (pin "1") (pinfunction "1_1") (pintype "passive"))
    )
    (net (code "142") (name "Net-(CN9-Pad21)") (class "Default")
      (node (ref "CN9") (pin "21") (pinfunction "21_21") (pintype "passive"))
      (node (ref "SB126") (pin "1") (pinfunction "1_1") (pintype "passive"))
      (node (ref "SB176") (pin "1") (pinfunction "1_1") (pintype "passive"))
    )
    (net (code "143") (name "Net-(CN10-Pad11)") (class "Default")
      (node (ref "CN10") (pin "11") (pinfunction "11_11") (pintype "passive"))
      (node (ref "SB158") (pin "2") (pinfunction "2_2") (pintype "passive"))
      (node (ref "SB159") (pin "2") (pinfunction "2_2") (pintype "passive"))
    )
    (net (code "144") (name "Net-(CN10-Pad14)") (class "Default")
      (node (ref "CN10") (pin "14") (pinfunction "14_14") (pintype "passive"))
      (node (ref "SB130") (pin "2") (pinfunction "2_2") (pintype "passive"))
      (node (ref "SB131") (pin "2") (pinfunction "2_2") (pintype "passive"))
      (node (ref "SB151") (pin "2") (pinfunction "2_2") (pintype "passive"))
    )
    (net (code "145") (name "Net-(CN10-Pad16)") (class "Default")
      (node (ref "CN10") (pin "16") (pinfunction "16_16") (pintype "passive"))
      (node (ref "SB134") (pin "2") (pinfunction "2_2") (pintype "passive"))
      (node (ref "SB135") (pin "2") (pinfunction "2_2") (pintype "passive"))
      (node (ref "SB141") (pin "2") (pinfunction "2_2") (pintype "passive"))
    )
    (net (code "146") (name "Net-(CN10-Pad19)") (class "Default")
      (node (ref "CN10") (pin "19") (pinfunction "19_19") (pintype "passive"))
      (node (ref "SB10") (pin "2") (pinfunction "2_2") (pintype "passive"))
      (node (ref "SB168") (pin "2") (pinfunction "2_2") (pintype "passive"))
    )
    (net (code "147") (name "Net-(CN10-Pad21)") (class "Default")
      (node (ref "CN10") (pin "21") (pinfunction "21_21") (pintype "passive"))
      (node (ref "SB14") (pin "2") (pinfunction "2_2") (pintype "passive"))
      (node (ref "SB172") (pin "2") (pinfunction "2_2") (pintype "passive"))
    )
    (net (code "148") (name "Net-(CN10-Pad23)") (class "Default")
      (node (ref "CN10") (pin "23") (pinfunction "23_23") (pintype "passive"))
      (node (ref "SB15") (pin "2") (pinfunction "2_2") (pintype "passive"))
      (node (ref "SB175") (pin "2") (pinfunction "2_2") (pintype "passive"))
    )
    (net (code "149") (name "Net-(CN10-Pad29)") (class "Default")
      (node (ref "CN10") (pin "29") (pinfunction "29_29") (pintype "passive"))
      (node (ref "SB179") (pin "2") (pinfunction "2_2") (pintype "passive"))
    )
    (net (code "150") (name "Net-(CN11-Pad25)") (class "Default")
      (node (ref "CN11") (pin "25") (pinfunction "25_25") (pintype "passive"))
      (node (ref "SB144") (pin "2") (pinfunction "2_2") (pintype "passive"))
    )
    (net (code "151") (name "Net-(CN11-Pad27)") (class "Default")
      (node (ref "CN11") (pin "27") (pinfunction "27_27") (pintype "passive"))
      (node (ref "SB145") (pin "2") (pinfunction "2_2") (pintype "passive"))
    )
    (net (code "152") (name "Net-(CN11-Pad29)") (class "Default")
      (node (ref "CN11") (pin "29") (pinfunction "29_29") (pintype "passive"))
      (node (ref "SB148") (pin "2") (pinfunction "2_2") (pintype "passive"))
    )
    (net (code "153") (name "Net-(CN11-Pad31)") (class "Default")
      (node (ref "CN11") (pin "31") (pinfunction "31_31") (pintype "passive"))
      (node (ref "SB163") (pin "2") (pinfunction "2_2") (pintype "passive"))
    )
    (net (code "154") (name "Net-(CN11-Pad69)") (class "Default")
      (node (ref "CN11") (pin "69") (pinfunction "69_69") (pintype "passive"))
      (node (ref "SB4") (pin "2") (pinfunction "2_2") (pintype "passive"))
    )
    (net (code "155") (name "Net-(CN12-Pad1)") (class "Default")
      (node (ref "CN12") (pin "1") (pinfunction "1_1") (pintype "passive"))
      (node (ref "SB117") (pin "2") (pinfunction "2_2") (pintype "passive"))
    )
    (net (code "156") (name "Net-(CN12-Pad2)") (class "Default")
      (node (ref "CN12") (pin "2") (pinfunction "2_2") (pintype "passive"))
      (node (ref "SB116") (pin "2") (pinfunction "2_2") (pintype "passive"))
    )
    (net (code "157") (name "Net-(CN12-Pad10)") (class "Default")
      (node (ref "CN12") (pin "10") (pinfunction "10_10") (pintype "passive"))
      (node (ref "SB7") (pin "1") (pinfunction "1_1") (pintype "passive"))
    )
    (net (code "158") (name "Net-(LD1-A)") (class "Default")
      (node (ref "LD1") (pin "1") (pinfunction "A_1") (pintype "passive"))
      (node (ref "R32") (pin "2") (pinfunction "2_2") (pintype "passive"))
    )
    (net (code "159") (name "Net-(R34-Pad2)") (class "Default")
      (node (ref "R34") (pin "2") (pinfunction "2_2") (pintype "passive"))
      (node (ref "SB119") (pin "1") (pinfunction "1_1") (pintype "passive"))
      (node (ref "SB120") (pin "2") (pinfunction "2_2") (pintype "passive"))
    )
    (net (code "160") (name "Net-(U7-IN+)") (class "Default")
      (node (ref "R33") (pin "1") (pinfunction "1_1") (pintype "passive"))
      (node (ref "R34") (pin "1") (pinfunction "1_1") (pintype "passive"))
      (node (ref "U7") (pin "1") (pinfunction "IN+_1") (pintype "input"))
    )
    (net (code "161") (name "Net-(U7-IN-)") (class "Default")
      (node (ref "R32") (pin "1") (pinfunction "1_1") (pintype "passive"))
      (node (ref "U7") (pin "3") (pinfunction "IN-_3") (pintype "input"))
      (node (ref "U7") (pin "4") (pinfunction "OUT_4") (pintype "output"))
    )
    (net (code "162") (name "U5V") (class "Default")
      (node (ref "CN12") (pin "8") (pinfunction "8_8") (pintype "passive"))
    )
    (net (code "163") (name "VBAT") (class "Default")
      (node (ref "CN11") (pin "33") (pinfunction "33_33") (pintype "passive"))
    )
    (net (code "164") (name "VDD") (class "Default")
      (node (ref "CN11") (pin "5") (pinfunction "5_5") (pintype "passive"))
    )
    (net (code "165") (name "VIN") (class "Default")
      (node (ref "CN11") (pin "24") (pinfunction "24_24") (pintype "passive"))
      (node (ref "CN8") (pin "15") (pinfunction "15_15") (pintype "passive"))
    )
    (net (code "166") (name "unconnected-(CN8-Pad1)") (class "Default")
      (node (ref "CN8") (pin "1") (pinfunction "1_1") (pintype "passive"))
    )
    (net (code "167") (name "unconnected-(CN11-Pad10)") (class "Default")
      (node (ref "CN11") (pin "10") (pinfunction "10_10") (pintype "passive"))
    )
    (net (code "168") (name "unconnected-(CN11-Pad26)") (class "Default")
      (node (ref "CN11") (pin "26") (pinfunction "26_26") (pintype "passive"))
    )
  )
)
